# 4_BLE-T1_power.net
KiCad netlist of a schematic drawn in Altium Designer
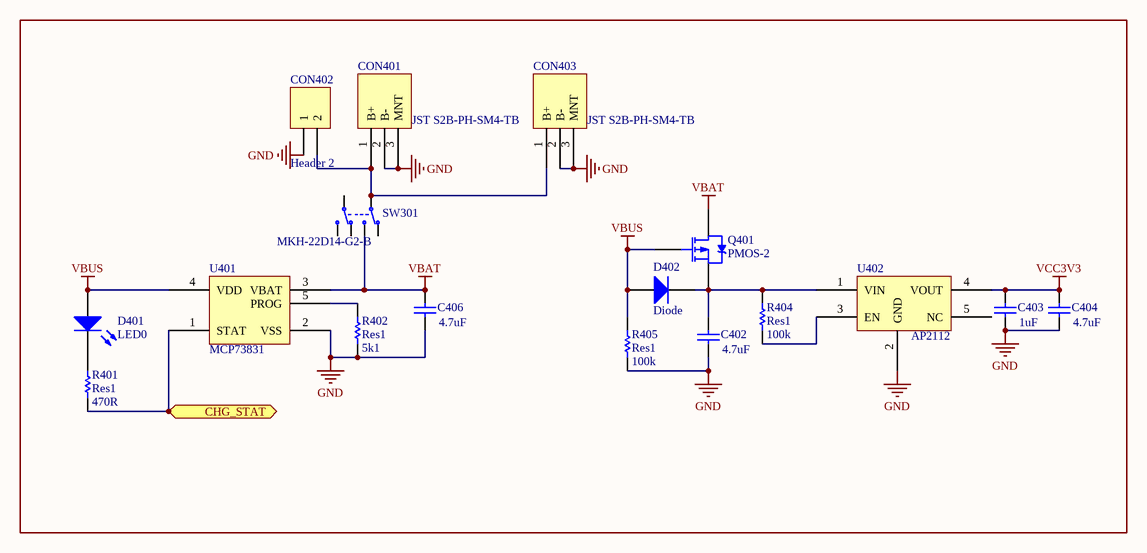
[diagram p0: 4_BLE-T1_power.SchDoc]

(export (version "E")
  (design (tool "Eeschema 10.0.6"))
  (components
    (comp (ref "C402")
      (value "4.7uF")
      (footprint "C1206[3216]")
      (description "Capacitor")
      (libsource (lib "Miscellaneous Devices") (part "Cap"))
    )
    (comp (ref "C403")
      (value "1uF")
      (footprint "C0603[1608]")
      (description "Capacitor")
      (fields (field (name "MFG") "KEMET") (field (name "MRF.PART") "1206B475K500NT"))
      (libsource (lib "Miscellaneous Devices") (part "Cap"))
    )
    (comp (ref "C404")
      (value "4.7uF")
      (footprint "C1206[3216]")
      (description "Capacitor")
      (libsource (lib "Miscellaneous Devices") (part "Cap"))
    )
    (comp (ref "C406")
      (value "4.7uF")
      (footprint "C1206[3216]")
      (description "Capacitor")
      (libsource (lib "Miscellaneous Devices") (part "Cap"))
    )
    (comp (ref "CON401")
      (value "JST S2B-PH-SM4-TB")
      (footprint "JST S2B-PH-SM4-TB")
      (fields (field (name "MFG") "JST Sales America Inc."))
      (libsource (lib "Keebs") (part "JST S2B-PH-SM4-TB"))
    )
    (comp (ref "CON402")
      (value "Header 2")
      (footprint "HDR1X2")
      (description "Header, 2-Pin")
      (libsource (lib "Miscellaneous Connectors") (part "Header 2"))
    )
    (comp (ref "CON403")
      (value "JST S2B-PH-SM4-TB")
      (footprint "JST SM02B-SRSS-TB")
      (fields (field (name "MFG") "JST Sales America Inc."))
      (libsource (lib "Keebs") (part "JST S2B-PH-SM4-TB"))
    )
    (comp (ref "D401")
      (value "LED0")
      (footprint "LED0603[1608]")
      (description "Typical INFRARED GaAs LED")
      (fields (field (name "MFG") "Kingbright"))
      (libsource (lib "Miscellaneous Devices") (part "LED0"))
    )
    (comp (ref "D402")
      (value "Diode")
      (footprint "D0603[1608]")
      (description "Default Diode")
      (fields (field (name "PUBLISHER") "Altium Limited"))
      (libsource (lib "Miscellaneous Devices") (part "Diode"))
    )
    (comp (ref "Q401")
      (value "PMOS-2")
      (footprint "SOT-23-3")
      (description "P-Channel Power MOSFET")
      (fields (field (name "PUBLISHER") "Altium Limited"))
      (libsource (lib "Miscellaneous Devices") (part "PMOS-2"))
    )
    (comp (ref "R401")
      (value "Res1")
      (footprint "R0603[1608]")
      (description "Resistor")
      (fields (field (name "ALTIUM_VALUE") "470R") (field (name "MFG") "TE Connectivity Passive Product"))
      (libsource (lib "Miscellaneous Devices") (part "Res1"))
    )
    (comp (ref "R402")
      (value "Res1")
      (footprint "R0603[1608]")
      (description "Resistor")
      (fields (field (name "ALTIUM_VALUE") "5k1") (field (name "MFG") "TE Connectivity Passive Product"))
      (libsource (lib "Miscellaneous Devices") (part "Res1"))
    )
    (comp (ref "R404")
      (value "Res1")
      (footprint "R0603[1608]")
      (description "Resistor")
      (fields (field (name "ALTIUM_VALUE") "100k") (field (name "MFG") "TE Connectivity Passive Product"))
      (libsource (lib "Miscellaneous Devices") (part "Res1"))
    )
    (comp (ref "R405")
      (value "Res1")
      (footprint "R0603[1608]")
      (description "Resistor")
      (fields (field (name "ALTIUM_VALUE") "100k") (field (name "MFG") "TE Connectivity Passive Product"))
      (libsource (lib "Miscellaneous Devices") (part "Res1"))
    )
    (comp (ref "SW301")
      (value "MKH-22D14-G2-B")
      (footprint "MKH-22D14-G2-B")
      (description "Slide Switch DPDT")
      (fields (field (name "MFG") "Nidec Copal Electronics"))
      (libsource (lib "Keebs") (part "MKH-22D14-G2-B"))
    )
    (comp (ref "U401") (value "MCP73831") (footprint "SOT-23-5") (libsource (lib "Keebs") (part "MCP73831")))
    (comp (ref "U402") (value "AP2112") (footprint "SOT-23-5") (libsource (lib "Keebs") (part "AP2112")))
  )
  (nets
    (net (code "1") (name "/CHG_STAT") (class "Default")
      (node (ref "R401") (pin "2") (pinfunction "2_2") (pintype "passive"))
      (node (ref "U401") (pin "1") (pinfunction "STAT_1") (pintype "passive"))
    )
    (net (code "2") (name "GND") (class "Default")
      (node (ref "C402") (pin "1") (pinfunction "1_1") (pintype "passive"))
      (node (ref "C403") (pin "1") (pinfunction "1_1") (pintype "passive"))
      (node (ref "C404") (pin "1") (pinfunction "1_1") (pintype "passive"))
      (node (ref "C406") (pin "1") (pinfunction "1_1") (pintype "passive"))
      (node (ref "CON401") (pin "2") (pinfunction "B-_2") (pintype "passive"))
      (node (ref "CON401") (pin "3") (pinfunction "MNT_3") (pintype "passive"))
      (node (ref "CON402") (pin "1") (pinfunction "1_1") (pintype "passive"))
      (node (ref "CON403") (pin "2") (pinfunction "B-_2") (pintype "passive"))
      (node (ref "CON403") (pin "3") (pinfunction "MNT_3") (pintype "passive"))
      (node (ref "R402") (pin "2") (pinfunction "2_2") (pintype "passive"))
      (node (ref "R405") (pin "2") (pinfunction "2_2") (pintype "passive"))
      (node (ref "U401") (pin "2") (pinfunction "VSS_2") (pintype "passive"))
      (node (ref "U402") (pin "2") (pinfunction "GND_2") (pintype "passive"))
    )
    (net (code "3") (name "Net-(CON401-B+)") (class "Default")
      (node (ref "CON401") (pin "1") (pinfunction "B+_1") (pintype "passive"))
      (node (ref "CON402") (pin "2") (pinfunction "2_2") (pintype "passive"))
      (node (ref "CON403") (pin "1") (pinfunction "B+_1") (pintype "passive"))
      (node (ref "SW301") (pin "2") (pinfunction "COM-1_2") (pintype "passive"))
    )
    (net (code "4") (name "Net-(D401-K)") (class "Default")
      (node (ref "D401") (pin "2") (pinfunction "K_2") (pintype "passive"))
      (node (ref "R401") (pin "1") (pinfunction "1_1") (pintype "passive"))
    )
    (net (code "5") (name "Net-(D402-K)") (class "Default")
      (node (ref "C402") (pin "2") (pinfunction "2_2") (pintype "passive"))
      (node (ref "D402") (pin "2") (pinfunction "K_2") (pintype "passive"))
      (node (ref "Q401") (pin "2") (pinfunction "S_2") (pintype "passive"))
      (node (ref "R404") (pin "1") (pinfunction "1_1") (pintype "passive"))
      (node (ref "U402") (pin "1") (pinfunction "VIN_1") (pintype "passive"))
    )
    (net (code "6") (name "Net-(U401-PROG)") (class "Default")
      (node (ref "R402") (pin "1") (pinfunction "1_1") (pintype "passive"))
      (node (ref "U401") (pin "5") (pinfunction "PROG_5") (pintype "passive"))
    )
    (net (code "7") (name "Net-(U402-EN)") (class "Default")
      (node (ref "R404") (pin "2") (pinfunction "2_2") (pintype "passive"))
      (node (ref "U402") (pin "3") (pinfunction "EN_3") (pintype "passive"))
    )
    (net (code "8") (name "VBAT") (class "Default")
      (node (ref "C406") (pin "2") (pinfunction "2_2") (pintype "passive"))
      (node (ref "Q401") (pin "3") (pinfunction "D_3") (pintype "passive"))
      (node (ref "SW301") (pin "1") (pinfunction "N.O-1_1") (pintype "passive"))
      (node (ref "U401") (pin "3") (pinfunction "VBAT_3") (pintype "passive"))
    )
    (net (code "9") (name "VBUS") (class "Default")
      (node (ref "D401") (pin "1") (pinfunction "A_1") (pintype "passive"))
      (node (ref "D402") (pin "1") (pinfunction "A_1") (pintype "passive"))
      (node (ref "Q401") (pin "1") (pinfunction "G_1") (pintype "passive"))
      (node (ref "R405") (pin "1") (pinfunction "1_1") (pintype "passive"))
      (node (ref "U401") (pin "4") (pinfunction "VDD_4") (pintype "passive"))
    )
    (net (code "10") (name "VCC3V3") (class "Default")
      (node (ref "C403") (pin "2") (pinfunction "2_2") (pintype "passive"))
      (node (ref "C404") (pin "2") (pinfunction "2_2") (pintype "passive"))
      (node (ref "U402") (pin "4") (pinfunction "VOUT_4") (pintype "passive"))
    )
    (net (code "11") (name "unconnected-(SW301-COM-2-Pad5)") (class "Default")
      (node (ref "SW301") (pin "5") (pinfunction "COM-2_5") (pintype "passive"))
    )
    (net (code "12") (name "unconnected-(SW301-N.C-1-Pad3)") (class "Default")
      (node (ref "SW301") (pin "3") (pinfunction "N.C-1_3") (pintype "passive"))
    )
    (net (code "13") (name "unconnected-(SW301-N.C-2-Pad6)") (class "Default")
      (node (ref "SW301") (pin "6") (pinfunction "N.C-2_6") (pintype "passive"))
    )
    (net (code "14") (name "unconnected-(SW301-N.O-2-Pad4)") (class "Default")
      (node (ref "SW301") (pin "4") (pinfunction "N.O-2_4") (pintype "passive"))
    )
    (net (code "15") (name "unconnected-(U402-NC-Pad5)") (class "Default")
      (node (ref "U402") (pin "5") (pinfunction "NC_5") (pintype "passive"))
    )
  )
)
